# DiPho_supply.net
KiCad netlist of a schematic drawn in Altium Designer
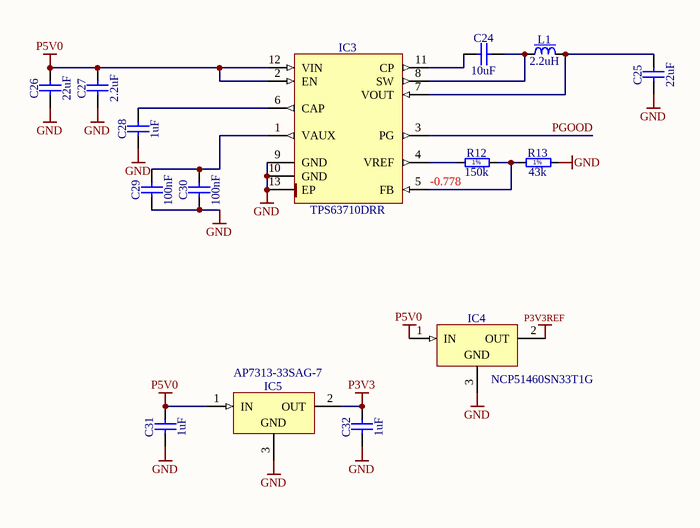
[diagram p0: DiPho supply.SchDoc]

(export (version "E")
  (design (tool "Eeschema 10.0.6"))
  (components
    (comp (ref "C24")
      (value "10uF")
      (footprint "CAPC2012X135N")
      (description "Non-polarised capacitor")
      (fields
        (field (name "PART NUMBER") "CC0805_10UF_16V_10%_X5R")
        (field (name "VOLTAGE") "16V")
        (field (name "AUTHOR") "CERN DEM JLC")
      )
      (libsource (lib "Capacitors") (part "Capacitor - non polarized"))
    )
    (comp (ref "C25")
      (value "22uF")
      (footprint "CAPC2012X135N")
      (description "Non-polarised capacitor")
      (fields
        (field (name "PART NUMBER") "CC0805_22UF_16V_10%_X5R")
        (field (name "VOLTAGE") "16V")
        (field (name "AUTHOR") "CERN DEM JLC")
      )
      (libsource (lib "Capacitors") (part "Capacitor - non polarized"))
    )
    (comp (ref "C26")
      (value "22uF")
      (footprint "CAPC2012X135N")
      (description "Non-polarised capacitor")
      (fields
        (field (name "PART NUMBER") "CC0805_22UF_16V_10%_X5R")
        (field (name "VOLTAGE") "16V")
        (field (name "AUTHOR") "CERN DEM JLC")
      )
      (libsource (lib "Capacitors") (part "Capacitor - non polarized"))
    )
    (comp (ref "C27")
      (value "2.2uF")
      (footprint "CAPC1608X87N")
      (description "Non-polarised capacitor")
      (fields
        (field (name "PART NUMBER") "CC0603_2.2UF_16V_10%_X5R")
        (field (name "VOLTAGE") "16V")
        (field (name "AUTHOR") "CERN DEM JLC")
      )
      (libsource (lib "Capacitors") (part "Capacitor - non polarized"))
    )
    (comp (ref "C28")
      (value "1uF")
      (footprint "CAPC1608X87N")
      (description "Non-polarised capacitor")
      (fields
        (field (name "PART NUMBER") "CC0603_1UF_16V_10%_X7R")
        (field (name "VOLTAGE") "16V")
        (field (name "AUTHOR") "CERN DEM JLC")
      )
      (libsource (lib "Capacitors") (part "Capacitor - non polarized"))
    )
    (comp (ref "C29")
      (value "100nF")
      (footprint "CAPC1005X55N")
      (description "Non-polarised capacitor")
      (fields
        (field (name "PART NUMBER") "CC0402_100NF_16V_10%_X5R")
        (field (name "VOLTAGE") "16V")
        (field (name "AUTHOR") "CERN DEM JLC")
      )
      (libsource (lib "Capacitors") (part "Capacitor - non polarized"))
    )
    (comp (ref "C30")
      (value "100nF")
      (footprint "CAPC1005X55N")
      (description "Non-polarised capacitor")
      (fields
        (field (name "PART NUMBER") "CC0402_100NF_16V_10%_X5R")
        (field (name "VOLTAGE") "16V")
        (field (name "AUTHOR") "CERN DEM JLC")
      )
      (libsource (lib "Capacitors") (part "Capacitor - non polarized"))
    )
    (comp (ref "C31")
      (value "1uF")
      (footprint "CAPC1608X87N")
      (description "Non-polarised capacitor")
      (fields
        (field (name "PART NUMBER") "CC0603_1UF_16V_10%_X7R")
        (field (name "VOLTAGE") "16V")
        (field (name "AUTHOR") "CERN DEM JLC")
      )
      (libsource (lib "Capacitors") (part "Capacitor - non polarized"))
    )
    (comp (ref "C32")
      (value "1uF")
      (footprint "CAPC1608X87N")
      (description "Non-polarised capacitor")
      (fields
        (field (name "PART NUMBER") "CC0603_1UF_16V_10%_X7R")
        (field (name "VOLTAGE") "16V")
        (field (name "AUTHOR") "CERN DEM JLC")
      )
      (libsource (lib "Capacitors") (part "Capacitor - non polarized"))
    )
    (comp (ref "IC3")
      (value "TPS63710DRR")
      (footprint "SON50P300X300X80-13N-R160X260")
      (description "-1 to -5.5VDC, 1A Output, Low Noise Synchronous Inverting Buck Converter")
      (fields (field (name "MANUFACTURER") "TEXAS INSTRUMENTS") (field (name "AUTHOR") "CERN DEM BC"))
      (libsource (lib "ICs And Semiconductors") (part "TPS63710"))
    )
    (comp (ref "IC4")
      (value "NCP51460SN33T1G")
      (footprint "SOT95P240X110-3N")
      (description "3-Terminal Regulator 1=IN 2=OUT 3=GND")
      (fields (field (name "MANUFACTURER") "ON SEMICONDUCTOR") (field (name "AUTHOR") "CERN DEM MR"))
      (libsource (lib "ICs And Semiconductors") (part "REG3 1IN-2OUT-3GND"))
    )
    (comp (ref "IC5")
      (value "AP7313-33SAG-7")
      (footprint "SOT95P240X130-3N")
      (description "3-Terminal Regulator 1=IN 2=OUT 3=GND")
      (fields (field (name "MANUFACTURER") "DIODES INCORPORATED") (field (name "AUTHOR") "CERN DEM JLC"))
      (libsource (lib "ICs And Semiconductors") (part "REG3 1IN-2OUT-3GND"))
    )
    (comp (ref "L1")
      (value "2.2uH")
      (footprint "INDM3225X210N")
      (description "Inductor With Core")
      (fields
        (field (name "PART NUMBER") "IND1210_2.2UH_10%_EPCOS_B82422A")
        (field (name "POWER") "270mA")
        (field (name "AUTHOR") "CERN DEM JLC")
      )
      (libsource (lib "Inductors & Transformers") (part "Inductor With Magnetic core"))
    )
    (comp (ref "R12")
      (value "150k")
      (footprint "RESC1005X40N")
      (description "Resistor - 1%")
      (fields
        (field (name "PART NUMBER") "R0402_150K_1%_0.0625W_100PPM")
        (field (name "POWER") "0.0625W")
        (field (name "AUTHOR") "CERN DEM JLC")
      )
      (libsource (lib "Resistors") (part "Resistor - 1%"))
    )
    (comp (ref "R13")
      (value "43k")
      (footprint "RESC1005X40N")
      (description "Resistor - 1%")
      (fields
        (field (name "PART NUMBER") "R0402_43K_1%_0.0625W_100PPM")
        (field (name "POWER") "0.0625W")
        (field (name "AUTHOR") "CERN DEM JLC")
      )
      (libsource (lib "Resistors") (part "Resistor - 1%"))
    )
  )
  (nets
    (net (code "1") (name "/PGOOD") (class "Default")
      (node (ref "IC3") (pin "3") (pinfunction "PG_3") (pintype "output"))
    )
    (net (code "2") (name "GND") (class "Default")
      (node (ref "C25") (pin "1") (pinfunction "1_1") (pintype "passive"))
      (node (ref "C26") (pin "1") (pinfunction "1_1") (pintype "passive"))
      (node (ref "C27") (pin "1") (pinfunction "1_1") (pintype "passive"))
      (node (ref "C28") (pin "1") (pinfunction "1_1") (pintype "passive"))
      (node (ref "C29") (pin "1") (pinfunction "1_1") (pintype "passive"))
      (node (ref "C30") (pin "1") (pinfunction "1_1") (pintype "passive"))
      (node (ref "C31") (pin "1") (pinfunction "1_1") (pintype "passive"))
      (node (ref "C32") (pin "1") (pinfunction "1_1") (pintype "passive"))
      (node (ref "IC3") (pin "10") (pinfunction "GND_10") (pintype "power_in"))
      (node (ref "IC3") (pin "13") (pinfunction "EP_13") (pintype "power_in"))
      (node (ref "IC3") (pin "9") (pinfunction "GND_9") (pintype "power_in"))
      (node (ref "IC4") (pin "3") (pinfunction "GND_3") (pintype "power_in"))
      (node (ref "IC5") (pin "3") (pinfunction "GND_3") (pintype "power_in"))
      (node (ref "R13") (pin "2") (pinfunction "2_2") (pintype "passive"))
    )
    (net (code "3") (name "Net-(IC3-CAP)") (class "Default")
      (node (ref "C28") (pin "2") (pinfunction "2_2") (pintype "passive"))
      (node (ref "IC3") (pin "6") (pinfunction "CAP_6") (pintype "output"))
    )
    (net (code "4") (name "Net-(IC3-CP)") (class "Default")
      (node (ref "C24") (pin "1") (pinfunction "1_1") (pintype "passive"))
      (node (ref "IC3") (pin "11") (pinfunction "CP_11") (pintype "output"))
    )
    (net (code "5") (name "Net-(IC3-FB)") (class "Default")
      (node (ref "IC3") (pin "5") (pinfunction "FB_5") (pintype "input"))
      (node (ref "R12") (pin "2") (pinfunction "2_2") (pintype "passive"))
      (node (ref "R13") (pin "1") (pinfunction "1_1") (pintype "passive"))
    )
    (net (code "6") (name "Net-(IC3-SW)") (class "Default")
      (node (ref "C24") (pin "2") (pinfunction "2_2") (pintype "passive"))
      (node (ref "IC3") (pin "8") (pinfunction "SW_8") (pintype "output"))
      (node (ref "L1") (pin "1") (pinfunction "1_1") (pintype "passive"))
    )
    (net (code "7") (name "Net-(IC3-VAUX)") (class "Default")
      (node (ref "C29") (pin "2") (pinfunction "2_2") (pintype "passive"))
      (node (ref "C30") (pin "2") (pinfunction "2_2") (pintype "passive"))
      (node (ref "IC3") (pin "1") (pinfunction "VAUX_1") (pintype "output"))
    )
    (net (code "8") (name "Net-(IC3-VOUT)") (class "Default")
      (node (ref "C25") (pin "2") (pinfunction "2_2") (pintype "passive"))
      (node (ref "IC3") (pin "7") (pinfunction "VOUT_7") (pintype "input"))
      (node (ref "L1") (pin "2") (pinfunction "2_2") (pintype "passive"))
    )
    (net (code "9") (name "Net-(IC3-VREF)") (class "Default")
      (node (ref "IC3") (pin "4") (pinfunction "VREF_4") (pintype "output"))
      (node (ref "R12") (pin "1") (pinfunction "1_1") (pintype "passive"))
    )
    (net (code "10") (name "P3V3") (class "Default")
      (node (ref "C32") (pin "2") (pinfunction "2_2") (pintype "passive"))
      (node (ref "IC5") (pin "2") (pinfunction "OUT_2") (pintype "power_in"))
    )
    (net (code "11") (name "P3V3REF") (class "Default")
      (node (ref "IC4") (pin "2") (pinfunction "OUT_2") (pintype "power_in"))
    )
    (net (code "12") (name "P5V0") (class "Default")
      (node (ref "C26") (pin "2") (pinfunction "2_2") (pintype "passive"))
      (node (ref "C27") (pin "2") (pinfunction "2_2") (pintype "passive"))
      (node (ref "C31") (pin "2") (pinfunction "2_2") (pintype "passive"))
      (node (ref "IC3") (pin "12") (pinfunction "VIN_12") (pintype "input"))
      (node (ref "IC3") (pin "2") (pinfunction "EN_2") (pintype "input"))
      (node (ref "IC4") (pin "1") (pinfunction "IN_1") (pintype "input"))
      (node (ref "IC5") (pin "1") (pinfunction "IN_1") (pintype "input"))
    )
  )
)
